# Gagabiro_supply_interface.net
KiCad netlist of a schematic drawn in Altium Designer
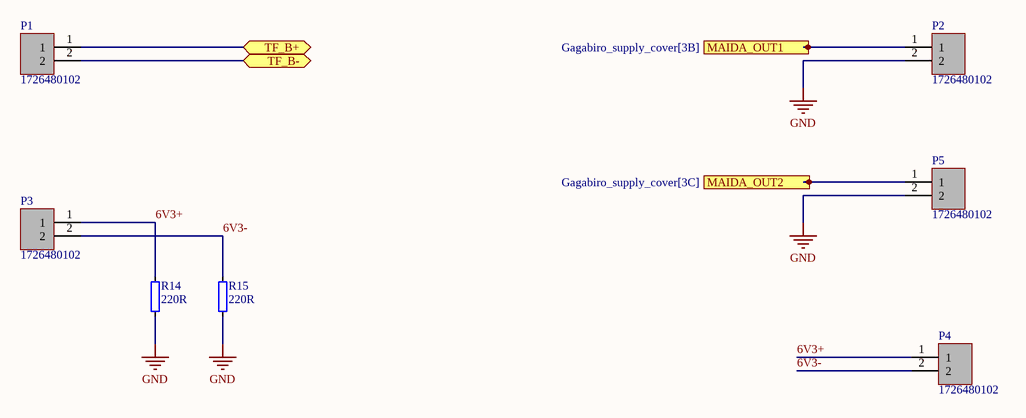
[diagram p0: Gagabiro_supply_interface.SchDoc]

(export (version "E")
  (design (tool "Eeschema 10.0.6"))
  (components
    (comp (ref "P1")
      (value "1726480102")
      (footprint "MOLEX_1726480102")
      (description "Connector Header Surface Mount, Right Angle 2 position 0.079 (2.00mm)")
      (fields (field (name "MP") "S2B-PH-SM4-TB") (field (name "MF") "JST Sales"))
      (libsource (lib "Persephone_Integrated_Library") (part "1726480102"))
    )
    (comp (ref "P2")
      (value "1726480102")
      (footprint "MOLEX_1726480102")
      (description "Connector Header Surface Mount, Right Angle 2 position 0.079 (2.00mm)")
      (fields (field (name "MP") "S2B-PH-SM4-TB") (field (name "MF") "JST Sales"))
      (libsource (lib "") (part "1726480102_1"))
    )
    (comp (ref "P3")
      (value "1726480102")
      (footprint "MOLEX_1726480102")
      (description "Connector Header Surface Mount, Right Angle 2 position 0.079 (2.00mm)")
      (fields (field (name "MP") "S2B-PH-SM4-TB") (field (name "MF") "JST Sales"))
      (libsource (lib "Persephone_Integrated_Library") (part "1726480102"))
    )
    (comp (ref "P4")
      (value "1726480102")
      (footprint "MOLEX_1726480102")
      (description "Connector Header Surface Mount, Right Angle 2 position 0.079 (2.00mm)")
      (fields (field (name "MP") "S2B-PH-SM4-TB") (field (name "MF") "JST Sales"))
      (libsource (lib "") (part "1726480102_1"))
    )
    (comp (ref "P5")
      (value "1726480102")
      (footprint "MOLEX_1726480102")
      (description "Connector Header Surface Mount, Right Angle 2 position 0.079 (2.00mm)")
      (fields (field (name "MP") "S2B-PH-SM4-TB") (field (name "MF") "JST Sales"))
      (libsource (lib "") (part "1726480102_1"))
    )
    (comp (ref "R14")
      (value "220R")
      (footprint "RES_2W_vertical")
      (description "Resistor, 2W")
      (fields (field (name "PART NUMBER") "R2W") (field (name "AUTHOR") "colombari"))
      (libsource (lib "Persephone_Integrated_Library") (part "R_2W_vertical_220R"))
    )
    (comp (ref "R15")
      (value "220R")
      (footprint "RES_2W_vertical")
      (description "Resistor, 2W")
      (fields (field (name "PART NUMBER") "R2W") (field (name "AUTHOR") "colombari"))
      (libsource (lib "Persephone_Integrated_Library") (part "R_2W_vertical_220R"))
    )
  )
  (nets
    (net (code "1") (name "/6V3+") (class "Default")
      (node (ref "P3") (pin "1") (pinfunction "1_1") (pintype "passive"))
      (node (ref "P4") (pin "1") (pinfunction "1_1") (pintype "passive"))
      (node (ref "R14") (pin "2") (pinfunction "2_2") (pintype "passive"))
    )
    (net (code "2") (name "/6V3-") (class "Default")
      (node (ref "P3") (pin "2") (pinfunction "2_2") (pintype "passive"))
      (node (ref "P4") (pin "2") (pinfunction "2_2") (pintype "passive"))
      (node (ref "R15") (pin "2") (pinfunction "2_2") (pintype "passive"))
    )
    (net (code "3") (name "/MAIDA_OUT1") (class "Default")
      (node (ref "P2") (pin "1") (pinfunction "1_1") (pintype "passive"))
    )
    (net (code "4") (name "/MAIDA_OUT2") (class "Default")
      (node (ref "P5") (pin "1") (pinfunction "1_1") (pintype "passive"))
    )
    (net (code "5") (name "/TF_B+") (class "Default")
      (node (ref "P1") (pin "1") (pinfunction "1_1") (pintype "passive"))
    )
    (net (code "6") (name "/TF_B-") (class "Default")
      (node (ref "P1") (pin "2") (pinfunction "2_2") (pintype "passive"))
    )
    (net (code "7") (name "GND") (class "Default")
      (node (ref "P2") (pin "2") (pinfunction "2_2") (pintype "passive"))
      (node (ref "P5") (pin "2") (pinfunction "2_2") (pintype "passive"))
      (node (ref "R14") (pin "1") (pinfunction "1_1") (pintype "passive"))
      (node (ref "R15") (pin "1") (pinfunction "1_1") (pintype "passive"))
    )
  )
)
